# Black_Magic_SCH.net
KiCad netlist of a schematic drawn in Altium Designer
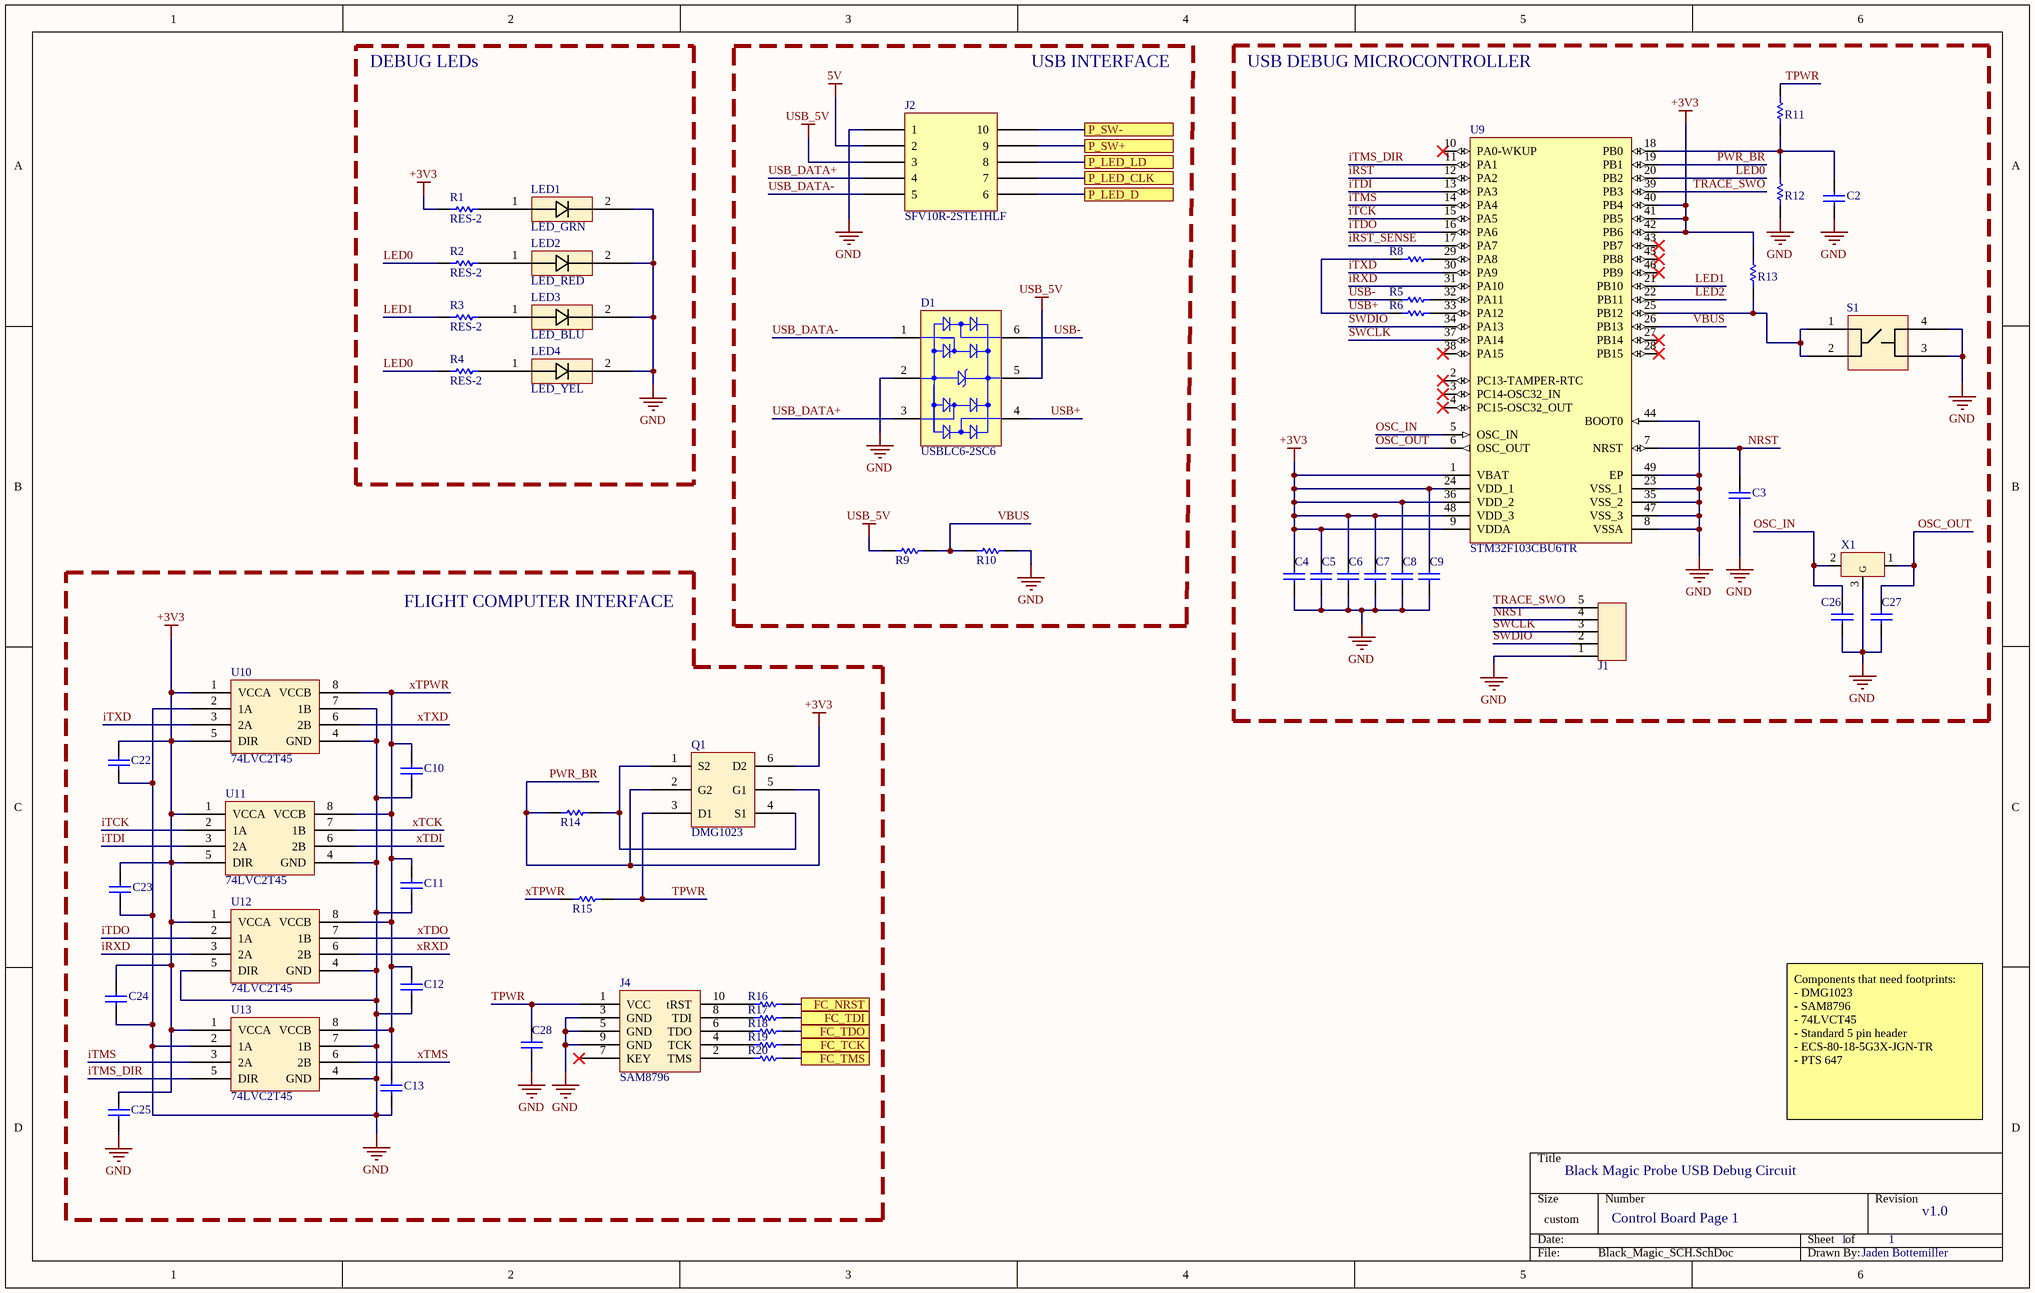
[diagram p0: Black_Magic_SCH.SchDoc]

(export (version "E")
  (design (tool "Eeschema 10.0.6"))
  (components
    (comp (ref "C2")
      (value "CAP0402")
      (footprint "CAPC0402(1005)60_L")
      (description "0402 (1005 Metric) Chip Capacitor")
      (libsource (lib "Altium Content Vault") (part "CAP_5"))
    )
    (comp (ref "C3")
      (value "CAP0402")
      (footprint "CAPC0402(1005)60_L")
      (description "0402 (1005 Metric) Chip Capacitor")
      (libsource (lib "Altium Content Vault") (part "CAP_5"))
    )
    (comp (ref "C4")
      (value "CAP0402")
      (footprint "CAPC0402(1005)60_L")
      (description "0402 (1005 Metric) Chip Capacitor")
      (libsource (lib "Altium Content Vault") (part "CAP_5"))
    )
    (comp (ref "C5")
      (value "CAP0402")
      (footprint "CAPC0402(1005)60_L")
      (description "0402 (1005 Metric) Chip Capacitor")
      (libsource (lib "Altium Content Vault") (part "CAP_5"))
    )
    (comp (ref "C6")
      (value "CAP0402")
      (footprint "CAPC0402(1005)60_L")
      (description "0402 (1005 Metric) Chip Capacitor")
      (libsource (lib "Altium Content Vault") (part "CAP_5"))
    )
    (comp (ref "C7")
      (value "CAP0402")
      (footprint "CAPC0402(1005)60_L")
      (description "0402 (1005 Metric) Chip Capacitor")
      (libsource (lib "Altium Content Vault") (part "CAP_5"))
    )
    (comp (ref "C8")
      (value "CAP0402")
      (footprint "CAPC0402(1005)60_L")
      (description "0402 (1005 Metric) Chip Capacitor")
      (libsource (lib "Altium Content Vault") (part "CAP_5"))
    )
    (comp (ref "C9")
      (value "CAP0402")
      (footprint "CAPC0402(1005)60_L")
      (description "0402 (1005 Metric) Chip Capacitor")
      (libsource (lib "Altium Content Vault") (part "CAP_5"))
    )
    (comp (ref "C10")
      (value "CAP0402")
      (footprint "CAPC0402(1005)60_L")
      (description "0402 (1005 Metric) Chip Capacitor")
      (libsource (lib "Altium Content Vault") (part "CAP_5"))
    )
    (comp (ref "C11")
      (value "CAP0402")
      (footprint "CAPC0402(1005)60_L")
      (description "0402 (1005 Metric) Chip Capacitor")
      (libsource (lib "Altium Content Vault") (part "CAP_5"))
    )
    (comp (ref "C12")
      (value "CAP0402")
      (footprint "CAPC0402(1005)60_L")
      (description "0402 (1005 Metric) Chip Capacitor")
      (libsource (lib "Altium Content Vault") (part "CAP_5"))
    )
    (comp (ref "C13")
      (value "CAP0402")
      (footprint "CAPC0402(1005)60_L")
      (description "0402 (1005 Metric) Chip Capacitor")
      (libsource (lib "Altium Content Vault") (part "CAP_5"))
    )
    (comp (ref "C22")
      (value "CAP0402")
      (footprint "CAPC0402(1005)60_L")
      (description "0402 (1005 Metric) Chip Capacitor")
      (libsource (lib "Altium Content Vault") (part "CAP_5"))
    )
    (comp (ref "C23")
      (value "CAP0402")
      (footprint "CAPC0402(1005)60_L")
      (description "0402 (1005 Metric) Chip Capacitor")
      (libsource (lib "Altium Content Vault") (part "CAP_5"))
    )
    (comp (ref "C24")
      (value "CAP0402")
      (footprint "CAPC0402(1005)60_L")
      (description "0402 (1005 Metric) Chip Capacitor")
      (libsource (lib "Altium Content Vault") (part "CAP_5"))
    )
    (comp (ref "C25")
      (value "CAP0402")
      (footprint "CAPC0402(1005)60_L")
      (description "0402 (1005 Metric) Chip Capacitor")
      (libsource (lib "Altium Content Vault") (part "CAP_5"))
    )
    (comp (ref "C26")
      (value "CAP0402")
      (footprint "CAPC0402(1005)60_L")
      (description "0402 (1005 Metric) Chip Capacitor")
      (libsource (lib "Altium Content Vault") (part "CAP_5"))
    )
    (comp (ref "C27")
      (value "CAP0402")
      (footprint "CAPC0402(1005)60_L")
      (description "0402 (1005 Metric) Chip Capacitor")
      (libsource (lib "Altium Content Vault") (part "CAP_5"))
    )
    (comp (ref "C28")
      (value "CAP0402")
      (footprint "CAPC0402(1005)60_L")
      (description "0402 (1005 Metric) Chip Capacitor")
      (libsource (lib "Altium Content Vault") (part "CAP_5"))
    )
    (comp (ref "D1")
      (value "USBLC6-2SC6")
      (footprint "STM-SOT23-6L_V")
      (description "Very low capacitance ESD protection, 3.5 pF, -40 to 125 degC, 6-Pin SOT23, RoHS, Tape and Reel")
      (fields (field (name "MANUFACTURER") "STMicroelectronics"))
      (libsource (lib "Altium Content Vault") (part "STM-USB_DVI_HDMIULC6-4SC6X-SOT23-6L"))
    )
    (comp (ref "J1") (value "5PIN_Standard") (libsource (lib "Copter") (part "5PIN_Standard")))
    (comp (ref "J2") (value "SFV10R-2STE1HLF") (libsource (lib "Copter") (part "SFV10R-2STE1HLF")))
    (comp (ref "J4") (value "SAM8796") (libsource (lib "Copter") (part "SAM8796")))
    (comp (ref "LED1")
      (value "LED_GRN")
      (footprint "DIOC3212X08N")
      (libsource (lib "Copter") (part "LED_GRN"))
    )
    (comp (ref "LED2")
      (value "LED_RED")
      (footprint "DIOC3212X08N")
      (libsource (lib "Copter") (part "LED_GRN"))
    )
    (comp (ref "LED3")
      (value "LED_BLU")
      (footprint "DIOC3212X08N")
      (libsource (lib "Copter") (part "LED_GRN"))
    )
    (comp (ref "LED4")
      (value "LED_YEL")
      (footprint "DIOC3212X08N")
      (libsource (lib "Copter") (part "LED_GRN"))
    )
    (comp (ref "Q1") (value "DMG1023") (libsource (lib "Copter") (part "DMG1023")))
    (comp (ref "R1") (value "RES-2") (footprint "RES 0402") (libsource (lib "Copter") (part "RES")))
    (comp (ref "R2") (value "RES-2") (footprint "RES 0402") (libsource (lib "Copter") (part "RES")))
    (comp (ref "R3") (value "RES-2") (footprint "RES 0402") (libsource (lib "Copter") (part "RES")))
    (comp (ref "R4") (value "RES-2") (footprint "RES 0402") (libsource (lib "Copter") (part "RES")))
    (comp (ref "R5") (value "RES-2") (footprint "RES 0402") (libsource (lib "Copter") (part "RES")))
    (comp (ref "R6") (value "RES-2") (footprint "RES 0402") (libsource (lib "Copter") (part "RES")))
    (comp (ref "R8") (value "RES-2") (footprint "RES 0402") (libsource (lib "Copter") (part "RES")))
    (comp (ref "R9") (value "RES-2") (footprint "RES 0402") (libsource (lib "Copter") (part "RES")))
    (comp (ref "R10") (value "RES-2") (footprint "RES 0402") (libsource (lib "Copter") (part "RES")))
    (comp (ref "R11") (value "RES-2") (footprint "RES 0402") (libsource (lib "Copter") (part "RES")))
    (comp (ref "R12") (value "RES-2") (footprint "RES 0402") (libsource (lib "Copter") (part "RES")))
    (comp (ref "R13") (value "RES-2") (footprint "RES 0402") (libsource (lib "Copter") (part "RES")))
    (comp (ref "R14") (value "RES-2") (footprint "RES 0402") (libsource (lib "Copter") (part "RES")))
    (comp (ref "R15") (value "RES-2") (footprint "RES 0402") (libsource (lib "Copter") (part "RES")))
    (comp (ref "R16") (value "RES-2") (footprint "RES 0402") (libsource (lib "Copter") (part "RES")))
    (comp (ref "R17") (value "RES-2") (footprint "RES 0402") (libsource (lib "Copter") (part "RES")))
    (comp (ref "R18") (value "RES-2") (footprint "RES 0402") (libsource (lib "Copter") (part "RES")))
    (comp (ref "R19") (value "RES-2") (footprint "RES 0402") (libsource (lib "Copter") (part "RES")))
    (comp (ref "R20") (value "RES-2") (footprint "RES 0402") (libsource (lib "Copter") (part "RES")))
    (comp (ref "S1") (value "PTS 647") (libsource (lib "Copter") (part "TactileSW")))
    (comp (ref "U9")
      (value "STM32F103CBU6TR")
      (footprint "STM-UFQFPN48_L")
      (libsource (lib "Altium Content Vault") (part "MC-ARM-STM32F103-UFQFPN48"))
    )
    (comp (ref "U10") (value "74LVC2T45") (libsource (lib "Copter") (part "74LVC2T45")))
    (comp (ref "U11") (value "74LVC2T45") (libsource (lib "Copter") (part "74LVC2T45")))
    (comp (ref "U12") (value "74LVC2T45") (libsource (lib "Copter") (part "74LVC2T45")))
    (comp (ref "U13") (value "74LVC2T45") (libsource (lib "Copter") (part "74LVC2T45")))
    (comp (ref "X1")
      (value "ECS-80-18-5G3X-JGN-TR")
      (libsource (lib "Copter") (part "ECS-80-18-5G3X-JGN-TR"))
    )
  )
  (nets
    (net (code "1") (name "+3V3") (class "Default")
      (node (ref "C22") (pin "2") (pinfunction "2_2") (pintype "passive"))
      (node (ref "C23") (pin "2") (pinfunction "2_2") (pintype "passive"))
      (node (ref "C24") (pin "2") (pinfunction "2_2") (pintype "passive"))
      (node (ref "C25") (pin "2") (pinfunction "2_2") (pintype "passive"))
      (node (ref "C4") (pin "2") (pinfunction "2_2") (pintype "passive"))
      (node (ref "C5") (pin "2") (pinfunction "2_2") (pintype "passive"))
      (node (ref "C6") (pin "2") (pinfunction "2_2") (pintype "passive"))
      (node (ref "C7") (pin "2") (pinfunction "2_2") (pintype "passive"))
      (node (ref "C8") (pin "2") (pinfunction "2_2") (pintype "passive"))
      (node (ref "C9") (pin "2") (pinfunction "2_2") (pintype "passive"))
      (node (ref "Q1") (pin "6") (pinfunction "D2_6") (pintype "passive"))
      (node (ref "R1") (pin "1") (pinfunction "1_1") (pintype "passive"))
      (node (ref "R13") (pin "1") (pinfunction "1_1") (pintype "passive"))
      (node (ref "U10") (pin "1") (pinfunction "VCCA_1") (pintype "passive"))
      (node (ref "U10") (pin "5") (pinfunction "DIR_5") (pintype "passive"))
      (node (ref "U11") (pin "1") (pinfunction "VCCA_1") (pintype "passive"))
      (node (ref "U11") (pin "5") (pinfunction "DIR_5") (pintype "passive"))
      (node (ref "U12") (pin "1") (pinfunction "VCCA_1") (pintype "passive"))
      (node (ref "U13") (pin "1") (pinfunction "VCCA_1") (pintype "passive"))
      (node (ref "U9") (pin "1") (pinfunction "VBAT_1") (pintype "power_in"))
      (node (ref "U9") (pin "24") (pinfunction "VDD_1_24") (pintype "power_in"))
      (node (ref "U9") (pin "36") (pinfunction "VDD_2_36") (pintype "power_in"))
      (node (ref "U9") (pin "40") (pinfunction "PB4_40") (pintype "bidirectional"))
      (node (ref "U9") (pin "41") (pinfunction "PB5_41") (pintype "bidirectional"))
      (node (ref "U9") (pin "42") (pinfunction "PB6_42") (pintype "bidirectional"))
      (node (ref "U9") (pin "48") (pinfunction "VDD_3_48") (pintype "power_in"))
      (node (ref "U9") (pin "9") (pinfunction "VDDA_9") (pintype "power_in"))
    )
    (net (code "2") (name "/FC_NRST") (class "Default")
      (node (ref "R16") (pin "1") (pinfunction "1_1") (pintype "passive"))
    )
    (net (code "3") (name "/FC_TCK") (class "Default")
      (node (ref "R19") (pin "1") (pinfunction "1_1") (pintype "passive"))
    )
    (net (code "4") (name "/FC_TDI") (class "Default")
      (node (ref "R17") (pin "1") (pinfunction "1_1") (pintype "passive"))
    )
    (net (code "5") (name "/FC_TDO") (class "Default")
      (node (ref "R18") (pin "1") (pinfunction "1_1") (pintype "passive"))
    )
    (net (code "6") (name "/FC_TMS") (class "Default")
      (node (ref "R20") (pin "1") (pinfunction "1_1") (pintype "passive"))
    )
    (net (code "7") (name "/LED0") (class "Default")
      (node (ref "R2") (pin "1") (pinfunction "1_1") (pintype "passive"))
      (node (ref "R4") (pin "1") (pinfunction "1_1") (pintype "passive"))
      (node (ref "U9") (pin "20") (pinfunction "PB2_20") (pintype "bidirectional"))
    )
    (net (code "8") (name "/LED1") (class "Default")
      (node (ref "R3") (pin "1") (pinfunction "1_1") (pintype "passive"))
      (node (ref "U9") (pin "21") (pinfunction "PB10_21") (pintype "bidirectional"))
    )
    (net (code "9") (name "/LED2") (class "Default")
      (node (ref "U9") (pin "22") (pinfunction "PB11_22") (pintype "bidirectional"))
    )
    (net (code "10") (name "/NRST") (class "Default")
      (node (ref "C3") (pin "2") (pinfunction "2_2") (pintype "passive"))
      (node (ref "J1") (pin "4") (pinfunction "A_4") (pintype "passive"))
      (node (ref "U9") (pin "7") (pinfunction "NRST_7") (pintype "bidirectional"))
    )
    (net (code "11") (name "/OSC_IN") (class "Default")
      (node (ref "C26") (pin "2") (pinfunction "2_2") (pintype "passive"))
      (node (ref "U9") (pin "5") (pinfunction "OSC_IN_5") (pintype "input"))
      (node (ref "X1") (pin "2") (pinfunction "IN/OUT_2") (pintype "passive"))
    )
    (net (code "12") (name "/OSC_OUT") (class "Default")
      (node (ref "C27") (pin "2") (pinfunction "2_2") (pintype "passive"))
      (node (ref "U9") (pin "6") (pinfunction "OSC_OUT_6") (pintype "output"))
      (node (ref "X1") (pin "1") (pinfunction "IN/OUT_1") (pintype "passive"))
    )
    (net (code "13") (name "/PWR_BR") (class "Default")
      (node (ref "Q1") (pin "2") (pinfunction "G2_2") (pintype "passive"))
      (node (ref "Q1") (pin "5") (pinfunction "G1_5") (pintype "passive"))
      (node (ref "R14") (pin "2") (pinfunction "2_2") (pintype "passive"))
      (node (ref "U9") (pin "19") (pinfunction "PB1_19") (pintype "bidirectional"))
    )
    (net (code "14") (name "/P_LED_CLK") (class "Default")
      (node (ref "J2") (pin "7") (pinfunction "7_7") (pintype "passive"))
    )
    (net (code "15") (name "/P_LED_D") (class "Default")
      (node (ref "J2") (pin "6") (pinfunction "6_6") (pintype "passive"))
    )
    (net (code "16") (name "/P_LED_LD") (class "Default")
      (node (ref "J2") (pin "8") (pinfunction "8_8") (pintype "passive"))
    )
    (net (code "17") (name "/P_SW+") (class "Default")
      (node (ref "J2") (pin "9") (pinfunction "9_9") (pintype "passive"))
    )
    (net (code "18") (name "/P_SW-") (class "Default")
      (node (ref "J2") (pin "10") (pinfunction "10_10") (pintype "passive"))
    )
    (net (code "19") (name "/SWCLK") (class "Default")
      (node (ref "J1") (pin "3") (pinfunction "A_3") (pintype "passive"))
      (node (ref "U9") (pin "37") (pinfunction "PA14_37") (pintype "bidirectional"))
    )
    (net (code "20") (name "/SWDIO") (class "Default")
      (node (ref "J1") (pin "2") (pinfunction "A_2") (pintype "passive"))
      (node (ref "U9") (pin "34") (pinfunction "PA13_34") (pintype "bidirectional"))
    )
    (net (code "21") (name "/TPWR") (class "Default")
      (node (ref "C28") (pin "2") (pinfunction "2_2") (pintype "passive"))
      (node (ref "J4") (pin "1") (pinfunction "VCC_1") (pintype "passive"))
      (node (ref "Q1") (pin "3") (pinfunction "D1_3") (pintype "passive"))
      (node (ref "R11") (pin "1") (pinfunction "1_1") (pintype "passive"))
      (node (ref "R15") (pin "1") (pinfunction "1_1") (pintype "passive"))
    )
    (net (code "22") (name "/TRACE_SWO") (class "Default")
      (node (ref "J1") (pin "5") (pinfunction "A_5") (pintype "passive"))
      (node (ref "U9") (pin "39") (pinfunction "PB3_39") (pintype "bidirectional"))
    )
    (net (code "23") (name "/USB+") (class "Default")
      (node (ref "D1") (pin "4") (pinfunction "I/O_3_4") (pintype "passive"))
      (node (ref "R6") (pin "1") (pinfunction "1_1") (pintype "passive"))
      (node (ref "R8") (pin "1") (pinfunction "1_1") (pintype "passive"))
    )
    (net (code "24") (name "/USB-") (class "Default")
      (node (ref "D1") (pin "6") (pinfunction "I/O_4_6") (pintype "passive"))
      (node (ref "R5") (pin "1") (pinfunction "1_1") (pintype "passive"))
    )
    (net (code "25") (name "/USB_DATA+") (class "Default")
      (node (ref "D1") (pin "3") (pinfunction "I/O_2_3") (pintype "passive"))
      (node (ref "J2") (pin "4") (pinfunction "4_4") (pintype "passive"))
    )
    (net (code "26") (name "/USB_DATA-") (class "Default")
      (node (ref "D1") (pin "1") (pinfunction "I/O_1_1") (pintype "passive"))
      (node (ref "J2") (pin "5") (pinfunction "5_5") (pintype "passive"))
    )
    (net (code "27") (name "/VBUS") (class "Default")
      (node (ref "R10") (pin "1") (pinfunction "1_1") (pintype "passive"))
      (node (ref "R9") (pin "1") (pinfunction "1_1") (pintype "passive"))
      (node (ref "U9") (pin "26") (pinfunction "PB13_26") (pintype "bidirectional"))
    )
    (net (code "28") (name "/iRST") (class "Default")
      (node (ref "U9") (pin "12") (pinfunction "PA2_12") (pintype "bidirectional"))
    )
    (net (code "29") (name "/iRST_SENSE") (class "Default")
      (node (ref "U9") (pin "17") (pinfunction "PA7_17") (pintype "bidirectional"))
    )
    (net (code "30") (name "/iRXD") (class "Default")
      (node (ref "U12") (pin "3") (pinfunction "2A_3") (pintype "passive"))
      (node (ref "U9") (pin "31") (pinfunction "PA10_31") (pintype "bidirectional"))
    )
    (net (code "31") (name "/iTCK") (class "Default")
      (node (ref "U11") (pin "2") (pinfunction "1A_2") (pintype "passive"))
      (node (ref "U9") (pin "15") (pinfunction "PA5_15") (pintype "bidirectional"))
    )
    (net (code "32") (name "/iTDI") (class "Default")
      (node (ref "U11") (pin "3") (pinfunction "2A_3") (pintype "passive"))
      (node (ref "U9") (pin "13") (pinfunction "PA3_13") (pintype "bidirectional"))
    )
    (net (code "33") (name "/iTDO") (class "Default")
      (node (ref "U12") (pin "2") (pinfunction "1A_2") (pintype "passive"))
      (node (ref "U9") (pin "16") (pinfunction "PA6_16") (pintype "bidirectional"))
    )
    (net (code "34") (name "/iTMS") (class "Default")
      (node (ref "U13") (pin "3") (pinfunction "2A_3") (pintype "passive"))
      (node (ref "U9") (pin "14") (pinfunction "PA4_14") (pintype "bidirectional"))
    )
    (net (code "35") (name "/iTMS_DIR") (class "Default")
      (node (ref "U13") (pin "5") (pinfunction "DIR_5") (pintype "passive"))
      (node (ref "U9") (pin "11") (pinfunction "PA1_11") (pintype "bidirectional"))
    )
    (net (code "36") (name "/iTXD") (class "Default")
      (node (ref "U10") (pin "3") (pinfunction "2A_3") (pintype "passive"))
      (node (ref "U9") (pin "30") (pinfunction "PA9_30") (pintype "bidirectional"))
    )
    (net (code "37") (name "/xRXD") (class "Default")
      (node (ref "U12") (pin "6") (pinfunction "2B_6") (pintype "passive"))
    )
    (net (code "38") (name "/xTCK") (class "Default")
      (node (ref "U11") (pin "7") (pinfunction "1B_7") (pintype "passive"))
    )
    (net (code "39") (name "/xTDI") (class "Default")
      (node (ref "U11") (pin "6") (pinfunction "2B_6") (pintype "passive"))
    )
    (net (code "40") (name "/xTDO") (class "Default")
      (node (ref "U12") (pin "7") (pinfunction "1B_7") (pintype "passive"))
    )
    (net (code "41") (name "/xTMS") (class "Default")
      (node (ref "U13") (pin "6") (pinfunction "2B_6") (pintype "passive"))
    )
    (net (code "42") (name "/xTPWR") (class "Default")
      (node (ref "C10") (pin "2") (pinfunction "2_2") (pintype "passive"))
      (node (ref "C11") (pin "2") (pinfunction "2_2") (pintype "passive"))
      (node (ref "C12") (pin "2") (pinfunction "2_2") (pintype "passive"))
      (node (ref "C13") (pin "2") (pinfunction "2_2") (pintype "passive"))
      (node (ref "R15") (pin "2") (pinfunction "2_2") (pintype "passive"))
      (node (ref "U10") (pin "8") (pinfunction "VCCB_8") (pintype "passive"))
      (node (ref "U11") (pin "8") (pinfunction "VCCB_8") (pintype "passive"))
      (node (ref "U12") (pin "8") (pinfunction "VCCB_8") (pintype "passive"))
      (node (ref "U13") (pin "8") (pinfunction "VCCB_8") (pintype "passive"))
    )
    (net (code "43") (name "/xTXD") (class "Default")
      (node (ref "U10") (pin "6") (pinfunction "2B_6") (pintype "passive"))
    )
    (net (code "44") (name "5V") (class "Default")
      (node (ref "J2") (pin "2") (pinfunction "2_2") (pintype "passive"))
    )
    (net (code "45") (name "GND") (class "Default")
      (node (ref "C10") (pin "1") (pinfunction "1_1") (pintype "passive"))
      (node (ref "C11") (pin "1") (pinfunction "1_1") (pintype "passive"))
      (node (ref "C12") (pin "1") (pinfunction "1_1") (pintype "passive"))
      (node (ref "C13") (pin "1") (pinfunction "1_1") (pintype "passive"))
      (node (ref "C2") (pin "1") (pinfunction "1_1") (pintype "passive"))
      (node (ref "C22") (pin "1") (pinfunction "1_1") (pintype "passive"))
      (node (ref "C23") (pin "1") (pinfunction "1_1") (pintype "passive"))
      (node (ref "C24") (pin "1") (pinfunction "1_1") (pintype "passive"))
      (node (ref "C25") (pin "1") (pinfunction "1_1") (pintype "passive"))
      (node (ref "C26") (pin "1") (pinfunction "1_1") (pintype "passive"))
      (node (ref "C27") (pin "1") (pinfunction "1_1") (pintype "passive"))
      (node (ref "C28") (pin "1") (pinfunction "1_1") (pintype "passive"))
      (node (ref "C3") (pin "1") (pinfunction "1_1") (pintype "passive"))
      (node (ref "C4") (pin "1") (pinfunction "1_1") (pintype "passive"))
      (node (ref "C5") (pin "1") (pinfunction "1_1") (pintype "passive"))
      (node (ref "C6") (pin "1") (pinfunction "1_1") (pintype "passive"))
      (node (ref "C7") (pin "1") (pinfunction "1_1") (pintype "passive"))
      (node (ref "C8") (pin "1") (pinfunction "1_1") (pintype "passive"))
      (node (ref "C9") (pin "1") (pinfunction "1_1") (pintype "passive"))
      (node (ref "D1") (pin "2") (pinfunction "GND_2") (pintype "passive"))
      (node (ref "J1") (pin "1") (pinfunction "A_1") (pintype "passive"))
      (node (ref "J2") (pin "1") (pinfunction "1_1") (pintype "passive"))
      (node (ref "J4") (pin "3") (pinfunction "GND_3") (pintype "passive"))
      (node (ref "J4") (pin "5") (pinfunction "GND_5") (pintype "passive"))
      (node (ref "J4") (pin "9") (pinfunction "GND_9") (pintype "passive"))
      (node (ref "LED1") (pin "2") (pinfunction "Cathode_2") (pintype "passive"))
      (node (ref "LED2") (pin "2") (pinfunction "Cathode_2") (pintype "passive"))
      (node (ref "LED3") (pin "2") (pinfunction "Cathode_2") (pintype "passive"))
      (node (ref "LED4") (pin "2") (pinfunction "Cathode_2") (pintype "passive"))
      (node (ref "R10") (pin "2") (pinfunction "2_2") (pintype "passive"))
      (node (ref "R12") (pin "2") (pinfunction "2_2") (pintype "passive"))
      (node (ref "S1") (pin "3") (pintype "passive"))
      (node (ref "S1") (pin "4") (pintype "passive"))
      (node (ref "U10") (pin "2") (pinfunction "1A_2") (pintype "passive"))
      (node (ref "U10") (pin "4") (pinfunction "GND_4") (pintype "passive"))
      (node (ref "U10") (pin "7") (pinfunction "1B_7") (pintype "passive"))
      (node (ref "U11") (pin "4") (pinfunction "GND_4") (pintype "passive"))
      (node (ref "U12") (pin "4") (pinfunction "GND_4") (pintype "passive"))
      (node (ref "U12") (pin "5") (pinfunction "DIR_5") (pintype "passive"))
      (node (ref "U13") (pin "2") (pinfunction "1A_2") (pintype "passive"))
      (node (ref "U13") (pin "4") (pinfunction "GND_4") (pintype "passive"))
      (node (ref "U13") (pin "7") (pinfunction "1B_7") (pintype "passive"))
      (node (ref "U9") (pin "23") (pinfunction "VSS_1_23") (pintype "power_in"))
      (node (ref "U9") (pin "35") (pinfunction "VSS_2_35") (pintype "power_in"))
      (node (ref "U9") (pin "44") (pinfunction "BOOT0_44") (pintype "input"))
      (node (ref "U9") (pin "47") (pinfunction "VSS_3_47") (pintype "power_in"))
      (node (ref "U9") (pin "49") (pinfunction "EP_49") (pintype "passive"))
      (node (ref "U9") (pin "8") (pinfunction "VSSA_8") (pintype "power_in"))
      (node (ref "X1") (pin "3") (pinfunction "G_3") (pintype "passive"))
    )
    (net (code "46") (name "Net-(J4-TCK)") (class "Default")
      (node (ref "J4") (pin "4") (pinfunction "TCK_4") (pintype "passive"))
      (node (ref "R19") (pin "2") (pinfunction "2_2") (pintype "passive"))
    )
    (net (code "47") (name "Net-(J4-TDI)") (class "Default")
      (node (ref "J4") (pin "8") (pinfunction "TDI_8") (pintype "passive"))
      (node (ref "R17") (pin "2") (pinfunction "2_2") (pintype "passive"))
    )
    (net (code "48") (name "Net-(J4-TDO)") (class "Default")
      (node (ref "J4") (pin "6") (pinfunction "TDO_6") (pintype "passive"))
      (node (ref "R18") (pin "2") (pinfunction "2_2") (pintype "passive"))
    )
    (net (code "49") (name "Net-(J4-TMS)") (class "Default")
      (node (ref "J4") (pin "2") (pinfunction "TMS_2") (pintype "passive"))
      (node (ref "R20") (pin "2") (pinfunction "2_2") (pintype "passive"))
    )
    (net (code "50") (name "Net-(J4-tRST)") (class "Default")
      (node (ref "J4") (pin "10") (pinfunction "tRST_10") (pintype "passive"))
      (node (ref "R16") (pin "2") (pinfunction "2_2") (pintype "passive"))
    )
    (net (code "51") (name "Net-(LED1-Anode)") (class "Default")
      (node (ref "LED1") (pin "1") (pinfunction "Anode_1") (pintype "passive"))
      (node (ref "R1") (pin "2") (pinfunction "2_2") (pintype "passive"))
    )
    (net (code "52") (name "Net-(LED2-Anode)") (class "Default")
      (node (ref "LED2") (pin "1") (pinfunction "Anode_1") (pintype "passive"))
      (node (ref "R2") (pin "2") (pinfunction "2_2") (pintype "passive"))
    )
    (net (code "53") (name "Net-(LED3-Anode)") (class "Default")
      (node (ref "LED3") (pin "1") (pinfunction "Anode_1") (pintype "passive"))
      (node (ref "R3") (pin "2") (pinfunction "2_2") (pintype "passive"))
    )
    (net (code "54") (name "Net-(LED4-Anode)") (class "Default")
      (node (ref "LED4") (pin "1") (pinfunction "Anode_1") (pintype "passive"))
      (node (ref "R4") (pin "2") (pinfunction "2_2") (pintype "passive"))
    )
    (net (code "55") (name "Net-(Q1-S1)") (class "Default")
      (node (ref "Q1") (pin "1") (pinfunction "S2_1") (pintype "passive"))
      (node (ref "Q1") (pin "4") (pinfunction "S1_4") (pintype "passive"))
      (node (ref "R14") (pin "1") (pinfunction "1_1") (pintype "passive"))
    )
    (net (code "56") (name "Net-(U9-PA8)") (class "Default")
      (node (ref "R8") (pin "2") (pinfunction "2_2") (pintype "passive"))
      (node (ref "U9") (pin "29") (pinfunction "PA8_29") (pintype "bidirectional"))
    )
    (net (code "57") (name "Net-(U9-PA11)") (class "Default")
      (node (ref "R5") (pin "2") (pinfunction "2_2") (pintype "passive"))
      (node (ref "U9") (pin "32") (pinfunction "PA11_32") (pintype "bidirectional"))
    )
    (net (code "58") (name "Net-(U9-PA12)") (class "Default")
      (node (ref "R6") (pin "2") (pinfunction "2_2") (pintype "passive"))
      (node (ref "U9") (pin "33") (pinfunction "PA12_33") (pintype "bidirectional"))
    )
    (net (code "59") (name "Net-(U9-PB0)") (class "Default")
      (node (ref "C2") (pin "2") (pinfunction "2_2") (pintype "passive"))
      (node (ref "R11") (pin "2") (pinfunction "2_2") (pintype "passive"))
      (node (ref "R12") (pin "1") (pinfunction "1_1") (pintype "passive"))
      (node (ref "U9") (pin "18") (pinfunction "PB0_18") (pintype "bidirectional"))
    )
    (net (code "60") (name "Net-(U9-PB12)") (class "Default")
      (node (ref "R13") (pin "2") (pinfunction "2_2") (pintype "passive"))
      (node (ref "S1") (pin "1") (pintype "passive"))
      (node (ref "S1") (pin "2") (pintype "passive"))
      (node (ref "U9") (pin "25") (pinfunction "PB12_25") (pintype "bidirectional"))
    )
    (net (code "61") (name "USB_5V") (class "Default")
      (node (ref "D1") (pin "5") (pinfunction "VBUS_5") (pintype "passive"))
      (node (ref "J2") (pin "3") (pinfunction "3_3") (pintype "passive"))
      (node (ref "R9") (pin "2") (pinfunction "2_2") (pintype "passive"))
    )
    (net (code "62") (name "unconnected-(J4-KEY-Pad7)") (class "Default")
      (node (ref "J4") (pin "7") (pinfunction "KEY_7") (pintype "passive+no_connect"))
    )
    (net (code "63") (name "unconnected-(U9-PA0-WKUP-Pad10)") (class "Default")
      (node (ref "U9") (pin "10") (pinfunction "PA0-WKUP_10") (pintype "bidirectional+no_connect"))
    )
    (net (code "64") (name "unconnected-(U9-PA15-Pad38)") (class "Default")
      (node (ref "U9") (pin "38") (pinfunction "PA15_38") (pintype "bidirectional+no_connect"))
    )
    (net (code "65") (name "unconnected-(U9-PB7-Pad43)") (class "Default")
      (node (ref "U9") (pin "43") (pinfunction "PB7_43") (pintype "bidirectional+no_connect"))
    )
    (net (code "66") (name "unconnected-(U9-PB8-Pad45)") (class "Default")
      (node (ref "U9") (pin "45") (pinfunction "PB8_45") (pintype "bidirectional+no_connect"))
    )
    (net (code "67") (name "unconnected-(U9-PB9-Pad46)") (class "Default")
      (node (ref "U9") (pin "46") (pinfunction "PB9_46") (pintype "bidirectional+no_connect"))
    )
    (net (code "68") (name "unconnected-(U9-PB14-Pad27)") (class "Default")
      (node (ref "U9") (pin "27") (pinfunction "PB14_27") (pintype "bidirectional+no_connect"))
    )
    (net (code "69") (name "unconnected-(U9-PB15-Pad28)") (class "Default")
      (node (ref "U9") (pin "28") (pinfunction "PB15_28") (pintype "bidirectional+no_connect"))
    )
    (net (code "70") (name "unconnected-(U9-PC13-TAMPER-RTC-Pad2)") (class "Default")
      (node (ref "U9") (pin "2") (pinfunction "PC13-TAMPER-RTC_2") (pintype "bidirectional+no_connect"))
    )
    (net (code "71") (name "unconnected-(U9-PC14-OSC32_IN-Pad3)") (class "Default")
      (node (ref "U9") (pin "3") (pinfunction "PC14-OSC32_IN_3") (pintype "bidirectional+no_connect"))
    )
    (net (code "72") (name "unconnected-(U9-PC15-OSC32_OUT-Pad4)") (class "Default")
      (node (ref "U9") (pin "4") (pinfunction "PC15-OSC32_OUT_4") (pintype "bidirectional+no_connect"))
    )
  )
)
